# mutteruhr-Haus.net
KiCad netlist of a schematic drawn in EAGLE
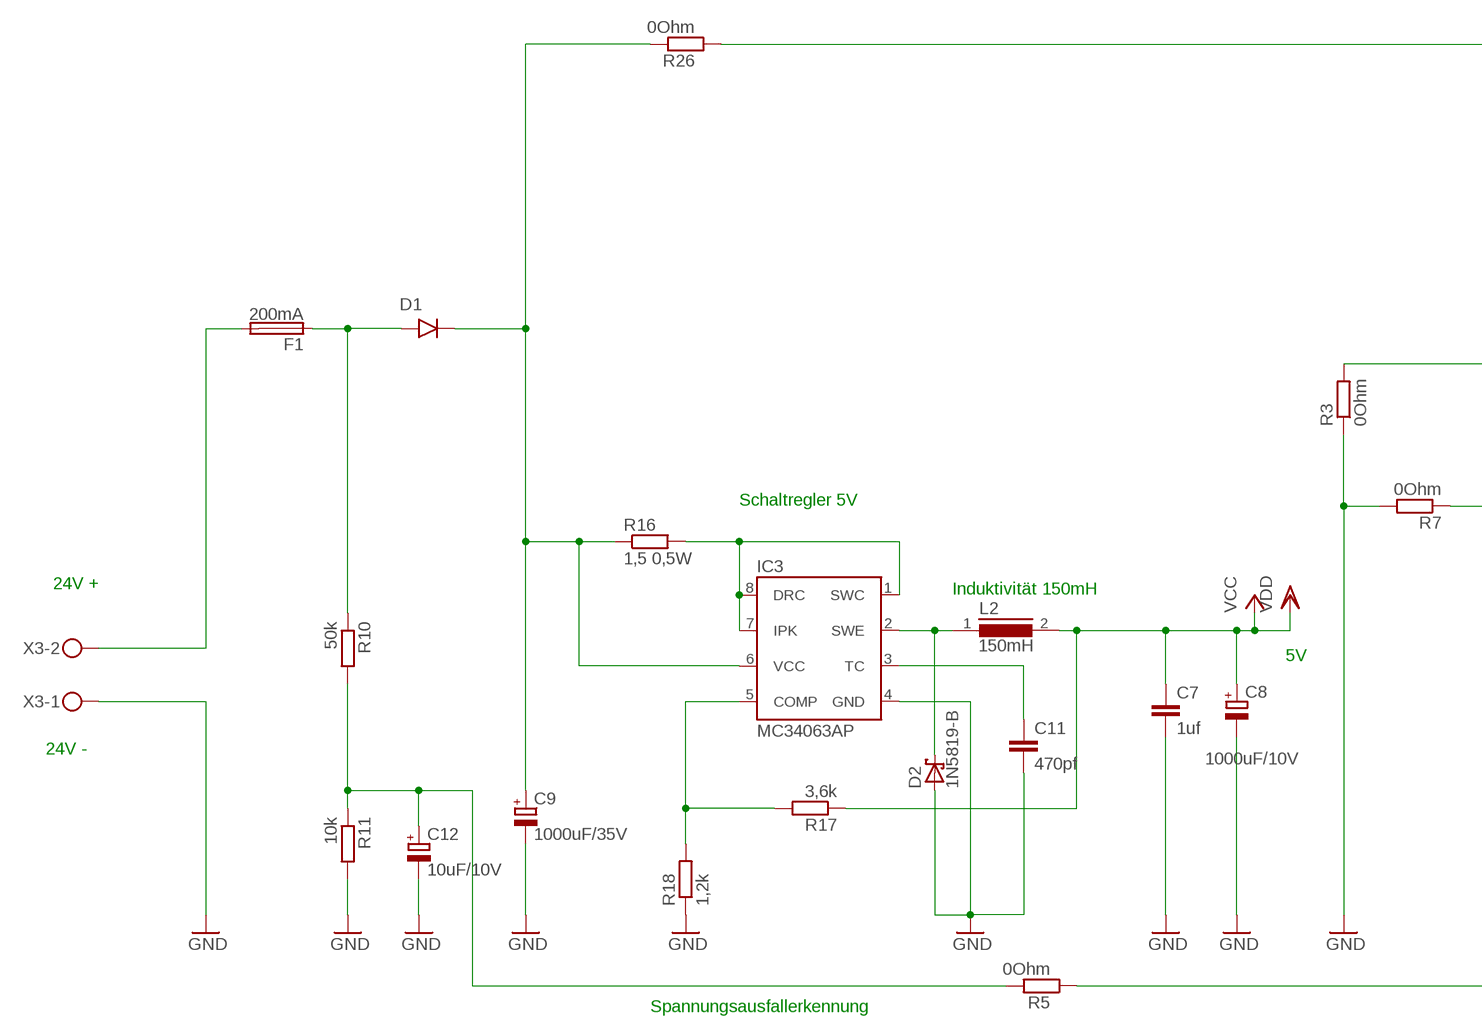
[diagram p0: schematic, sheet 1, part 1 of 2]
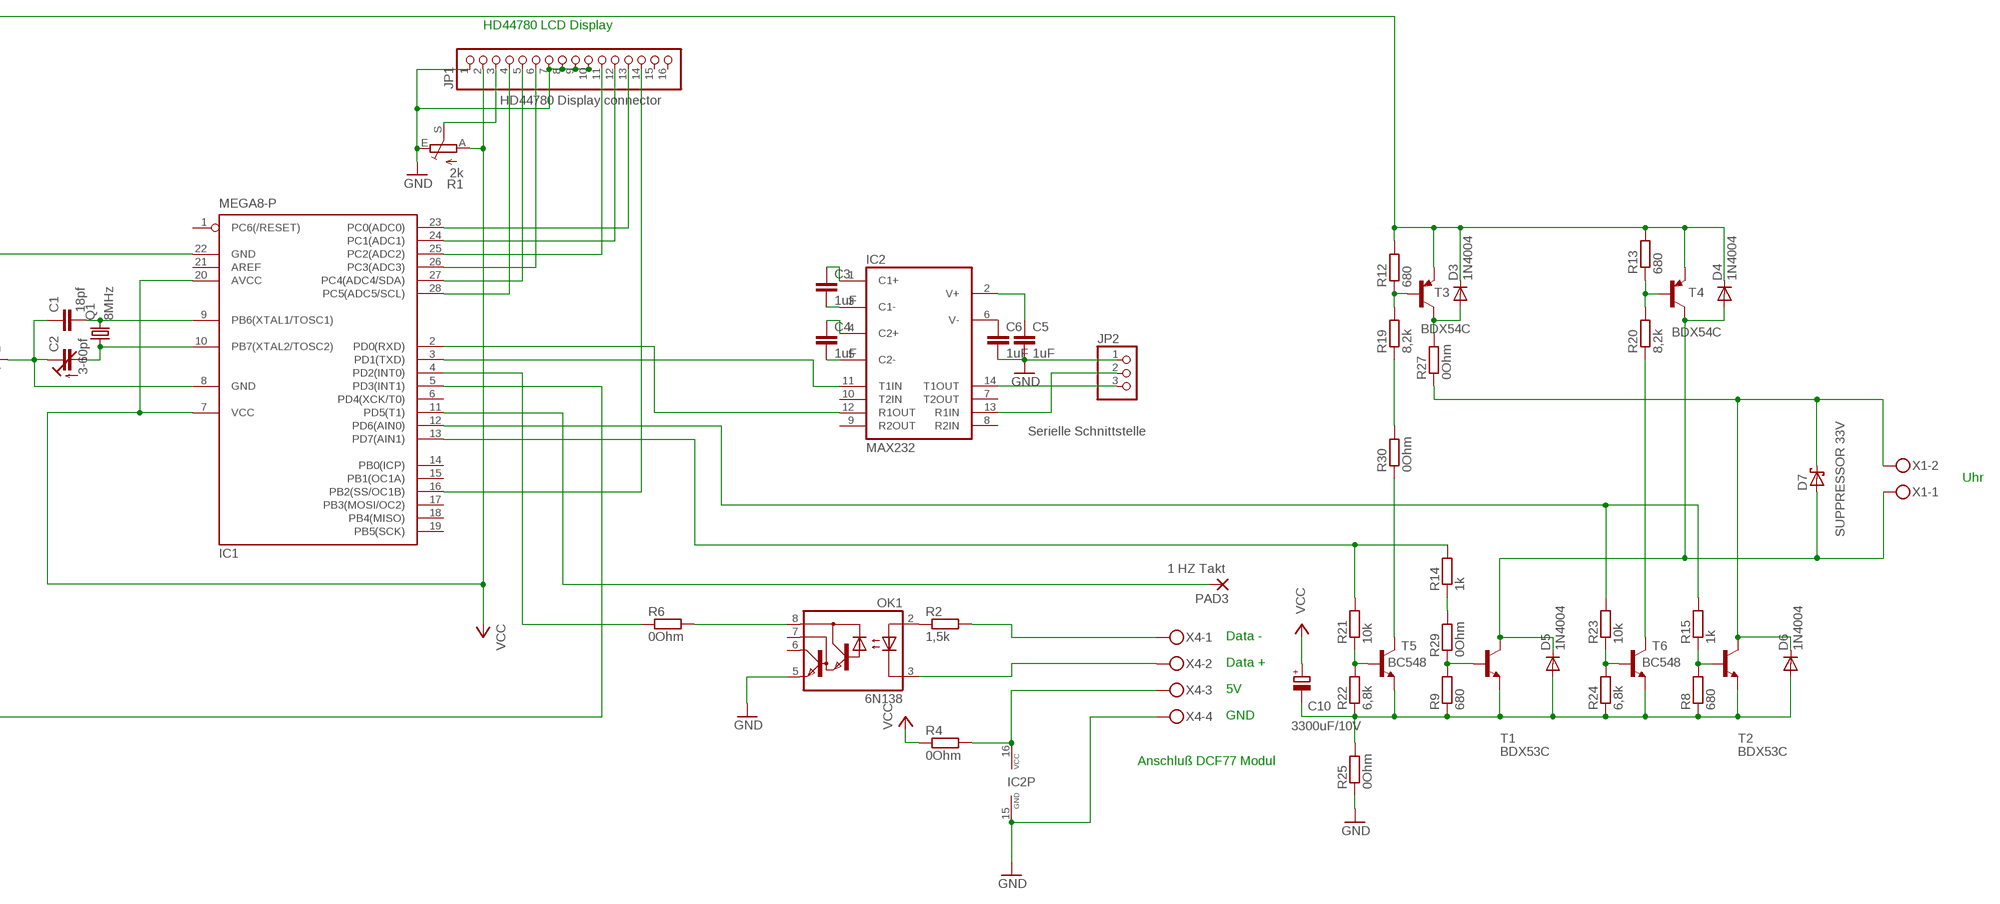
[diagram p1: schematic, sheet 1, part 2 of 2]

(export (version "E")
  (design (tool "Eeschema 10.0.6"))
  (components
    (comp (ref "C1")
      (value "18pf")
      (footprint "eagle-import:C050-024X044")
      (libsource (lib "eagle-import") (part "C-EU050-024X044"))
    )
    (comp (ref "C2")
      (value "3-60pf")
      (footprint "eagle-import:CTRIM3050.505")
      (libsource (lib "eagle-import") (part "C-TRIMM3050.505"))
    )
    (comp (ref "C3")
      (value "1uF")
      (footprint "eagle-import:C5B5.5")
      (libsource (lib "eagle-import") (part "C5/5.5"))
    )
    (comp (ref "C4")
      (value "1uF")
      (footprint "eagle-import:C5B5.5")
      (libsource (lib "eagle-import") (part "C5/5.5"))
    )
    (comp (ref "C5")
      (value "1uF")
      (footprint "eagle-import:C5B5.5")
      (libsource (lib "eagle-import") (part "C5/5.5"))
    )
    (comp (ref "C6")
      (value "1uF")
      (footprint "eagle-import:C5B5.5")
      (libsource (lib "eagle-import") (part "C5/5.5"))
    )
    (comp (ref "C7")
      (value "1uf")
      (footprint "eagle-import:C5B5.5")
      (libsource (lib "eagle-import") (part "C5/5.5"))
    )
    (comp (ref "C8")
      (value "1000uF/10V")
      (footprint "eagle-import:E5-8,5")
      (libsource (lib "eagle-import") (part "CPOL-EUE5-8.5"))
    )
    (comp (ref "C9")
      (value "1000uF/35V")
      (footprint "eagle-import:E5-8,5")
      (libsource (lib "eagle-import") (part "CPOL-EUE5-8.5"))
    )
    (comp (ref "C10")
      (value "3300uF/10V")
      (footprint "eagle-import:E7,5-16")
      (libsource (lib "eagle-import") (part "CPOL-EUE7.5-16"))
    )
    (comp (ref "C11")
      (value "470pf")
      (footprint "eagle-import:C5B5.5")
      (libsource (lib "eagle-import") (part "C5/5.5"))
    )
    (comp (ref "C12")
      (value "10uF/10V")
      (footprint "eagle-import:E5-5")
      (libsource (lib "eagle-import") (part "rcl-2_CPOL-EUE5-5"))
    )
    (comp (ref "D1")
      (value "1N4001")
      (footprint "eagle-import:DO41-10")
      (libsource (lib "eagle-import") (part "1N4001"))
    )
    (comp (ref "D2")
      (value "1N5819-B")
      (footprint "eagle-import:DO41-7.6")
      (libsource (lib "eagle-import") (part "1N5819-B"))
    )
    (comp (ref "D3")
      (value "1N4004")
      (footprint "eagle-import:DO41-10")
      (libsource (lib "eagle-import") (part "1N4004"))
    )
    (comp (ref "D4")
      (value "1N4004")
      (footprint "eagle-import:DO41-10")
      (libsource (lib "eagle-import") (part "1N4004"))
    )
    (comp (ref "D5")
      (value "1N4004")
      (footprint "eagle-import:DO41-10")
      (libsource (lib "eagle-import") (part "1N4004"))
    )
    (comp (ref "D6")
      (value "1N4004")
      (footprint "eagle-import:DO41-10")
      (libsource (lib "eagle-import") (part "1N4004"))
    )
    (comp (ref "D7")
      (value "SUPPRESSOR 33V")
      (footprint "eagle-import:DO41-10")
      (libsource (lib "eagle-import") (part "P4KEXX"))
    )
    (comp (ref "F1")
      (value "200mA")
      (footprint "eagle-import:GSH15")
      (fields (field (name "MPN") "64900001039"))
      (libsource (lib "eagle-import") (part "GSH15"))
    )
    (comp (ref "IC1")
      (value "MEGA8-P")
      (footprint "eagle-import:DIL28-3")
      (libsource (lib "eagle-import") (part "MEGA8-P"))
    )
    (comp (ref "IC2")
      (value "MAX232")
      (footprint "eagle-import:DIL16")
      (libsource (lib "eagle-import") (part "MAX232"))
    )
    (comp (ref "IC3")
      (value "MC34063AP")
      (footprint "eagle-import:DIL-08")
      (libsource (lib "eagle-import") (part "MC34063AP"))
    )
    (comp (ref "JP1")
      (value "HD44780 Display connector")
      (footprint "eagle-import:1X16")
      (libsource (lib "eagle-import") (part "PINHD-1X16_2.54"))
    )
    (comp (ref "JP2")
      (value "Serielle Schnittstelle")
      (footprint "eagle-import:1X03")
      (libsource (lib "eagle-import") (part "PINHD-1X3"))
    )
    (comp (ref "L2")
      (value "150mH")
      (footprint "eagle-import:82114R")
      (libsource (lib "eagle-import") (part "82114R"))
    )
    (comp (ref "OK1")
      (value "6N138")
      (footprint "eagle-import:DIL08")
      (fields (field (name "MF") "VISHAY/TELEFUNKEN"))
      (libsource (lib "eagle-import") (part "6N138"))
    )
    (comp (ref "PAD3")
      (value "1 HZ Takt")
      (footprint "eagle-import:2,54_0,8")
      (libsource (lib "eagle-import") (part "2,54/0,8"))
    )
    (comp (ref "Q1")
      (value "8MHz")
      (footprint "eagle-import:HC18U-V")
      (libsource (lib "eagle-import") (part "CRYSTALHC18U-V"))
    )
    (comp (ref "R1")
      (value "2k")
      (footprint "eagle-import:RS3")
      (libsource (lib "eagle-import") (part "TRIM_EU-RS3"))
    )
    (comp (ref "R2")
      (value "1,5k")
      (footprint "eagle-import:0204_7")
      (libsource (lib "eagle-import") (part "R-EU_0204/7"))
    )
    (comp (ref "R3")
      (value "0Ohm")
      (footprint "eagle-import:0204_7")
      (libsource (lib "eagle-import") (part "R-EU_0204/7"))
    )
    (comp (ref "R4")
      (value "0Ohm")
      (footprint "eagle-import:0204_7")
      (libsource (lib "eagle-import") (part "R-EU_0204/7"))
    )
    (comp (ref "R5")
      (value "0Ohm")
      (footprint "eagle-import:0204_7")
      (libsource (lib "eagle-import") (part "R-EU_0204/7"))
    )
    (comp (ref "R6")
      (value "0Ohm")
      (footprint "eagle-import:0204_7")
      (libsource (lib "eagle-import") (part "R-EU_0204/7"))
    )
    (comp (ref "R7")
      (value "0Ohm")
      (footprint "eagle-import:0204_7")
      (libsource (lib "eagle-import") (part "R-EU_0204/7"))
    )
    (comp (ref "R8")
      (value "680")
      (footprint "eagle-import:0207_10")
      (libsource (lib "eagle-import") (part "resistor_R-EU_0207/10"))
    )
    (comp (ref "R9")
      (value "680")
      (footprint "eagle-import:0207_10")
      (libsource (lib "eagle-import") (part "resistor_R-EU_0207/10"))
    )
    (comp (ref "R10")
      (value "50k")
      (footprint "eagle-import:0204_7")
      (libsource (lib "eagle-import") (part "R-EU_0204/7"))
    )
    (comp (ref "R11")
      (value "10k")
      (footprint "eagle-import:0204_7")
      (libsource (lib "eagle-import") (part "R-EU_0204/7"))
    )
    (comp (ref "R12")
      (value "680")
      (footprint "eagle-import:0207_10")
      (libsource (lib "eagle-import") (part "resistor_R-EU_0207/10"))
    )
    (comp (ref "R13")
      (value "680")
      (footprint "eagle-import:0207_10")
      (libsource (lib "eagle-import") (part "resistor_R-EU_0207/10"))
    )
    (comp (ref "R14")
      (value "1k")
      (footprint "eagle-import:0207_10")
      (libsource (lib "eagle-import") (part "resistor_R-EU_0207/10"))
    )
    (comp (ref "R15")
      (value "1k")
      (footprint "eagle-import:0207_10")
      (libsource (lib "eagle-import") (part "resistor_R-EU_0207/10"))
    )
    (comp (ref "R16")
      (value "1,5 0,5W")
      (footprint "eagle-import:0204_7")
      (libsource (lib "eagle-import") (part "R-EU_0204/7"))
    )
    (comp (ref "R17")
      (value "3,6k")
      (footprint "eagle-import:0204_7")
      (libsource (lib "eagle-import") (part "R-EU_0204/7"))
    )
    (comp (ref "R18")
      (value "1,2k")
      (footprint "eagle-import:0204_7")
      (libsource (lib "eagle-import") (part "R-EU_0204/7"))
    )
    (comp (ref "R19")
      (value "8,2k")
      (footprint "eagle-import:0207_10")
      (libsource (lib "eagle-import") (part "resistor_R-EU_0207/10"))
    )
    (comp (ref "R20")
      (value "8,2k")
      (footprint "eagle-import:0207_10")
      (libsource (lib "eagle-import") (part "resistor_R-EU_0207/10"))
    )
    (comp (ref "R21")
      (value "10k")
      (footprint "eagle-import:0207_10")
      (libsource (lib "eagle-import") (part "resistor_R-EU_0207/10"))
    )
    (comp (ref "R22")
      (value "6,8k")
      (footprint "eagle-import:0204V")
      (libsource (lib "eagle-import") (part "resistor_R-EU_0204/2V"))
    )
    (comp (ref "R23")
      (value "10k")
      (footprint "eagle-import:0207_10")
      (libsource (lib "eagle-import") (part "resistor_R-EU_0207/10"))
    )
    (comp (ref "R24")
      (value "6,8k")
      (footprint "eagle-import:0204V")
      (libsource (lib "eagle-import") (part "resistor_R-EU_0204/2V"))
    )
    (comp (ref "R25")
      (value "0Ohm")
      (footprint "eagle-import:0204_7")
      (libsource (lib "eagle-import") (part "R-EU_0204/7"))
    )
    (comp (ref "R26")
      (value "0Ohm")
      (footprint "eagle-import:0204_7")
      (libsource (lib "eagle-import") (part "R-EU_0204/7"))
    )
    (comp (ref "R27")
      (value "0Ohm")
      (footprint "eagle-import:0207_10")
      (libsource (lib "eagle-import") (part "resistor_R-EU_0207/10"))
    )
    (comp (ref "R29")
      (value "0Ohm")
      (footprint "eagle-import:0207_10")
      (libsource (lib "eagle-import") (part "resistor_R-EU_0207/10"))
    )
    (comp (ref "R30")
      (value "0Ohm")
      (footprint "eagle-import:0207_10")
      (libsource (lib "eagle-import") (part "resistor_R-EU_0207/10"))
    )
    (comp (ref "T1")
      (value "BDX53C")
      (footprint "eagle-import:TO220V")
      (libsource (lib "eagle-import") (part "-NPN-TO220V"))
    )
    (comp (ref "T2")
      (value "BDX53C")
      (footprint "eagle-import:TO220V")
      (libsource (lib "eagle-import") (part "-NPN-TO220V"))
    )
    (comp (ref "T3")
      (value "BDX54C")
      (footprint "eagle-import:TO220V")
      (libsource (lib "eagle-import") (part "-PNP-TO220V"))
    )
    (comp (ref "T4")
      (value "BDX54C")
      (footprint "eagle-import:TO220V")
      (libsource (lib "eagle-import") (part "-PNP-TO220V"))
    )
    (comp (ref "T5")
      (value "BC548")
      (footprint "eagle-import:TO92-EBC")
      (libsource (lib "eagle-import") (part "-NPN-TO92-EBC2N5551"))
    )
    (comp (ref "T6")
      (value "BC548")
      (footprint "eagle-import:TO92-EBC")
      (libsource (lib "eagle-import") (part "-NPN-TO92-EBC2N5551"))
    )
    (comp (ref "X1")
      (value "MKDSN1,5/2-5,08")
      (footprint "eagle-import:MKDSN1,5_2-5,08")
      (fields (field (name "MPN") "MKDSN 1,5/2-5.08"))
      (libsource (lib "eagle-import") (part "MKDSN1,5/2-5,08"))
    )
    (comp (ref "X3")
      (value "MKDSN1,5/2-5,08")
      (footprint "eagle-import:MKDSN1,5_2-5,08")
      (fields (field (name "MPN") "MKDSN 1,5/2-5.08"))
      (libsource (lib "eagle-import") (part "MKDSN1,5/2-5,08"))
    )
    (comp (ref "X4")
      (value "MKDSN1,5/4-5,08")
      (footprint "eagle-import:MKDSN1,5_4-5,08")
      (fields (field (name "MPN") "SMKDSN1,5/4-5,08"))
      (libsource (lib "eagle-import") (part "MKDSN1,5/4-5,08"))
    )
  )
  (nets
    (net (code "1") (name "GND") (class "Default")
      (node (ref "C11") (pin "2") (pinfunction "2_2") (pintype "passive"))
      (node (ref "C12") (pin "-") (pinfunction "-_-") (pintype "passive"))
      (node (ref "C5") (pin "2") (pinfunction "2_2") (pintype "passive"))
      (node (ref "C6") (pin "2") (pinfunction "2_2") (pintype "passive"))
      (node (ref "C7") (pin "2") (pinfunction "2_2") (pintype "passive"))
      (node (ref "C8") (pin "-") (pinfunction "-_-") (pintype "passive"))
      (node (ref "C9") (pin "-") (pinfunction "-_-") (pintype "passive"))
      (node (ref "D2") (pin "A") (pinfunction "A_A") (pintype "passive"))
      (node (ref "IC2") (pin "15") (pinfunction "GND_15") (pintype "power_in"))
      (node (ref "IC3") (pin "4") (pinfunction "GND_4") (pintype "power_in"))
      (node (ref "JP1") (pin "1") (pinfunction "1_1") (pintype "passive"))
      (node (ref "JP1") (pin "10") (pinfunction "10_10") (pintype "passive"))
      (node (ref "JP1") (pin "7") (pinfunction "7_7") (pintype "passive"))
      (node (ref "JP1") (pin "8") (pinfunction "8_8") (pintype "passive"))
      (node (ref "JP1") (pin "9") (pinfunction "9_9") (pintype "passive"))
      (node (ref "JP2") (pin "1") (pinfunction "1_1") (pintype "passive"))
      (node (ref "OK1") (pin "5") (pinfunction "GND_5") (pintype "passive"))
      (node (ref "R1") (pin "E") (pinfunction "E_E") (pintype "passive"))
      (node (ref "R11") (pin "2") (pinfunction "2_2") (pintype "passive"))
      (node (ref "R18") (pin "1") (pinfunction "1_1") (pintype "passive"))
      (node (ref "R25") (pin "1") (pinfunction "1_1") (pintype "passive"))
      (node (ref "R3") (pin "1") (pinfunction "1_1") (pintype "passive"))
      (node (ref "R7") (pin "2") (pinfunction "2_2") (pintype "passive"))
      (node (ref "X3") (pin "1") (pinfunction "KL_1") (pintype "passive"))
      (node (ref "X4") (pin "4") (pinfunction "KL_4") (pintype "passive"))
    )
    (net (code "2") (name "Net-(C2-A)") (class "Default")
      (node (ref "C2") (pin "2") (pinfunction "A_2") (pintype "passive"))
      (node (ref "IC1") (pin "10") (pinfunction "PB7(XTAL2/TOSC2)_10") (pintype "bidirectional"))
      (node (ref "Q1") (pin "1") (pinfunction "1_1") (pintype "passive"))
    )
    (net (code "3") (name "Net-(C2-E)") (class "Default")
      (node (ref "C1") (pin "1") (pinfunction "1_1") (pintype "passive"))
      (node (ref "C2") (pin "1") (pinfunction "E_1") (pintype "passive"))
      (node (ref "IC1") (pin "8") (pinfunction "GND_8") (pintype "power_in"))
      (node (ref "R7") (pin "1") (pinfunction "1_1") (pintype "passive"))
    )
    (net (code "4") (name "Net-(C12-Pad+)") (class "Default")
      (node (ref "C12") (pin "+") (pinfunction "+_+") (pintype "passive"))
      (node (ref "R10") (pin "2") (pinfunction "2_2") (pintype "passive"))
      (node (ref "R11") (pin "1") (pinfunction "1_1") (pintype "passive"))
      (node (ref "R5") (pin "2") (pinfunction "2_2") (pintype "passive"))
    )
    (net (code "5") (name "Net-(D1-ANODE)") (class "Default")
      (node (ref "D1") (pin "A") (pinfunction "ANODE_A") (pintype "passive"))
      (node (ref "F1") (pin "1") (pinfunction "1_1") (pintype "passive"))
      (node (ref "R10") (pin "1") (pinfunction "1_1") (pintype "passive"))
    )
    (net (code "6") (name "Net-(D1-CATHODE)") (class "Default")
      (node (ref "C9") (pin "+") (pinfunction "+_+") (pintype "passive"))
      (node (ref "D1") (pin "C") (pinfunction "CATHODE_C") (pintype "passive"))
      (node (ref "IC3") (pin "6") (pinfunction "VCC_6") (pintype "power_in"))
      (node (ref "R16") (pin "1") (pinfunction "1_1") (pintype "passive"))
      (node (ref "R26") (pin "2") (pinfunction "2_2") (pintype "passive"))
    )
    (net (code "7") (name "Net-(IC1-GND-Pad22)") (class "Default")
      (node (ref "IC1") (pin "22") (pinfunction "GND_22") (pintype "power_in"))
      (node (ref "R3") (pin "2") (pinfunction "2_2") (pintype "passive"))
    )
    (net (code "8") (name "Net-(IC1-PB2(SS{slash}OC1B))") (class "Default")
      (node (ref "IC1") (pin "16") (pinfunction "PB2(SS/OC1B)_16") (pintype "bidirectional"))
      (node (ref "JP1") (pin "14") (pinfunction "14_14") (pintype "passive"))
    )
    (net (code "9") (name "Net-(IC1-PB6(XTAL1{slash}TOSC1))") (class "Default")
      (node (ref "C1") (pin "2") (pinfunction "2_2") (pintype "passive"))
      (node (ref "IC1") (pin "9") (pinfunction "PB6(XTAL1/TOSC1)_9") (pintype "bidirectional"))
      (node (ref "Q1") (pin "2") (pinfunction "2_2") (pintype "passive"))
    )
    (net (code "10") (name "Net-(IC1-PC0(ADC0))") (class "Default")
      (node (ref "IC1") (pin "23") (pinfunction "PC0(ADC0)_23") (pintype "bidirectional"))
      (node (ref "JP1") (pin "13") (pinfunction "13_13") (pintype "passive"))
    )
    (net (code "11") (name "Net-(IC1-PC1(ADC1))") (class "Default")
      (node (ref "IC1") (pin "24") (pinfunction "PC1(ADC1)_24") (pintype "bidirectional"))
      (node (ref "JP1") (pin "12") (pinfunction "12_12") (pintype "passive"))
    )
    (net (code "12") (name "Net-(IC1-PC2(ADC2))") (class "Default")
      (node (ref "IC1") (pin "25") (pinfunction "PC2(ADC2)_25") (pintype "bidirectional"))
      (node (ref "JP1") (pin "11") (pinfunction "11_11") (pintype "passive"))
    )
    (net (code "13") (name "Net-(IC1-PC3(ADC3))") (class "Default")
      (node (ref "IC1") (pin "26") (pinfunction "PC3(ADC3)_26") (pintype "bidirectional"))
      (node (ref "JP1") (pin "6") (pinfunction "6_6") (pintype "passive"))
    )
    (net (code "14") (name "Net-(IC1-PC4(ADC4{slash}SDA))") (class "Default")
      (node (ref "IC1") (pin "27") (pinfunction "PC4(ADC4/SDA)_27") (pintype "bidirectional"))
      (node (ref "JP1") (pin "5") (pinfunction "5_5") (pintype "passive"))
    )
    (net (code "15") (name "Net-(IC1-PC5(ADC5{slash}SCL))") (class "Default")
      (node (ref "IC1") (pin "28") (pinfunction "PC5(ADC5/SCL)_28") (pintype "bidirectional"))
      (node (ref "JP1") (pin "4") (pinfunction "4_4") (pintype "passive"))
    )
    (net (code "16") (name "Net-(IC1-PD0(RXD))") (class "Default")
      (node (ref "IC1") (pin "2") (pinfunction "PD0(RXD)_2") (pintype "bidirectional"))
      (node (ref "IC2") (pin "12") (pinfunction "R1OUT_12") (pintype "output"))
    )
    (net (code "17") (name "Net-(IC1-PD1(TXD))") (class "Default")
      (node (ref "IC1") (pin "3") (pinfunction "PD1(TXD)_3") (pintype "bidirectional"))
      (node (ref "IC2") (pin "11") (pinfunction "T1IN_11") (pintype "input"))
    )
    (net (code "18") (name "Net-(IC1-PD2(INT0))") (class "Default")
      (node (ref "IC1") (pin "4") (pinfunction "PD2(INT0)_4") (pintype "bidirectional"))
      (node (ref "R6") (pin "1") (pinfunction "1_1") (pintype "passive"))
    )
    (net (code "19") (name "Net-(IC1-PD3(INT1))") (class "Default")
      (node (ref "IC1") (pin "5") (pinfunction "PD3(INT1)_5") (pintype "bidirectional"))
      (node (ref "R5") (pin "1") (pinfunction "1_1") (pintype "passive"))
    )
    (net (code "20") (name "Net-(IC1-PD5(T1))") (class "Default")
      (node (ref "IC1") (pin "11") (pinfunction "PD5(T1)_11") (pintype "bidirectional"))
      (node (ref "PAD3") (pin "1") (pinfunction "P_1") (pintype "passive"))
    )
    (net (code "21") (name "Net-(IC1-PD6(AIN0))") (class "Default")
      (node (ref "IC1") (pin "12") (pinfunction "PD6(AIN0)_12") (pintype "bidirectional"))
      (node (ref "R15") (pin "2") (pinfunction "2_2") (pintype "passive"))
      (node (ref "R23") (pin "2") (pinfunction "2_2") (pintype "passive"))
    )
    (net (code "22") (name "Net-(IC1-PD7(AIN1))") (class "Default")
      (node (ref "IC1") (pin "13") (pinfunction "PD7(AIN1)_13") (pintype "bidirectional"))
      (node (ref "R14") (pin "2") (pinfunction "2_2") (pintype "passive"))
      (node (ref "R21") (pin "2") (pinfunction "2_2") (pintype "passive"))
    )
    (net (code "23") (name "Net-(IC2A-C1+)") (class "Default")
      (node (ref "C3") (pin "1") (pinfunction "1_1") (pintype "passive"))
      (node (ref "IC2") (pin "1") (pinfunction "C1+_1") (pintype "bidirectional"))
    )
    (net (code "24") (name "Net-(IC2A-C1-)") (class "Default")
      (node (ref "C3") (pin "2") (pinfunction "2_2") (pintype "passive"))
      (node (ref "IC2") (pin "3") (pinfunction "C1-_3") (pintype "bidirectional"))
    )
    (net (code "25") (name "Net-(IC2A-C2+)") (class "Default")
      (node (ref "C4") (pin "1") (pinfunction "1_1") (pintype "passive"))
      (node (ref "IC2") (pin "4") (pinfunction "C2+_4") (pintype "bidirectional"))
    )
    (net (code "26") (name "Net-(IC2A-C2-)") (class "Default")
      (node (ref "C4") (pin "2") (pinfunction "2_2") (pintype "passive"))
      (node (ref "IC2") (pin "5") (pinfunction "C2-_5") (pintype "bidirectional"))
    )
    (net (code "27") (name "Net-(IC2A-R1IN)") (class "Default")
      (node (ref "IC2") (pin "13") (pinfunction "R1IN_13") (pintype "input"))
      (node (ref "JP2") (pin "2") (pinfunction "2_2") (pintype "passive"))
    )
    (net (code "28") (name "Net-(IC2A-T1OUT)") (class "Default")
      (node (ref "IC2") (pin "14") (pinfunction "T1OUT_14") (pintype "output"))
      (node (ref "JP2") (pin "3") (pinfunction "3_3") (pintype "passive"))
    )
    (net (code "29") (name "Net-(IC2A-V+)") (class "Default")
      (node (ref "C5") (pin "1") (pinfunction "1_1") (pintype "passive"))
      (node (ref "IC2") (pin "2") (pinfunction "V+_2") (pintype "bidirectional"))
    )
    (net (code "30") (name "Net-(IC2A-V-)") (class "Default")
      (node (ref "C6") (pin "1") (pinfunction "1_1") (pintype "passive"))
      (node (ref "IC2") (pin "6") (pinfunction "V-_6") (pintype "bidirectional"))
    )
    (net (code "31") (name "Net-(IC2B-VCC)") (class "Default")
      (node (ref "IC2") (pin "16") (pinfunction "VCC_16") (pintype "power_in"))
      (node (ref "R4") (pin "2") (pinfunction "2_2") (pintype "passive"))
      (node (ref "X4") (pin "3") (pinfunction "KL_3") (pintype "passive"))
    )
    (net (code "32") (name "Net-(IC3-COMP)") (class "Default")
      (node (ref "IC3") (pin "5") (pinfunction "COMP_5") (pintype "input"))
      (node (ref "R17") (pin "2") (pinfunction "2_2") (pintype "passive"))
      (node (ref "R18") (pin "2") (pinfunction "2_2") (pintype "passive"))
    )
    (net (code "33") (name "Net-(IC3-DRC)") (class "Default")
      (node (ref "IC3") (pin "1") (pinfunction "SWC_1") (pintype "bidirectional"))
      (node (ref "IC3") (pin "7") (pinfunction "IPK_7") (pintype "input"))
      (node (ref "IC3") (pin "8") (pinfunction "DRC_8") (pintype "input"))
      (node (ref "R16") (pin "2") (pinfunction "2_2") (pintype "passive"))
    )
    (net (code "34") (name "Net-(IC3-SWE)") (class "Default")
      (node (ref "D2") (pin "C") (pinfunction "C_C") (pintype "passive"))
      (node (ref "IC3") (pin "2") (pinfunction "SWE_2") (pintype "bidirectional"))
      (node (ref "L2") (pin "1") (pinfunction "1_1") (pintype "passive"))
    )
    (net (code "35") (name "Net-(IC3-TC)") (class "Default")
      (node (ref "C11") (pin "1") (pinfunction "1_1") (pintype "passive"))
      (node (ref "IC3") (pin "3") (pinfunction "TC_3") (pintype "passive"))
    )
    (net (code "36") (name "Net-(JP1-Pad3)") (class "Default")
      (node (ref "JP1") (pin "3") (pinfunction "3_3") (pintype "passive"))
      (node (ref "R1") (pin "S") (pinfunction "S_S") (pintype "passive"))
    )
    (net (code "37") (name "Net-(OK1-A)") (class "Default")
      (node (ref "OK1") (pin "2") (pinfunction "A_2") (pintype "passive"))
      (node (ref "R2") (pin "1") (pinfunction "1_1") (pintype "passive"))
    )
    (net (code "38") (name "Net-(OK1-C)") (class "Default")
      (node (ref "OK1") (pin "3") (pinfunction "C_3") (pintype "passive"))
      (node (ref "X4") (pin "2") (pinfunction "KL_2") (pintype "passive"))
    )
    (net (code "39") (name "Net-(OK1-VCC)") (class "Default")
      (node (ref "OK1") (pin "8") (pinfunction "VCC_8") (pintype "passive"))
      (node (ref "R6") (pin "2") (pinfunction "2_2") (pintype "passive"))
    )
    (net (code "40") (name "Net-(R14-Pad1)") (class "Default")
      (node (ref "R14") (pin "1") (pinfunction "1_1") (pintype "passive"))
      (node (ref "R29") (pin "2") (pinfunction "2_2") (pintype "passive"))
    )
    (net (code "41") (name "Net-(R19-Pad1)") (class "Default")
      (node (ref "R19") (pin "1") (pinfunction "1_1") (pintype "passive"))
      (node (ref "R30") (pin "2") (pinfunction "2_2") (pintype "passive"))
    )
    (net (code "42") (name "Net-(R20-Pad1)") (class "Default")
      (node (ref "R20") (pin "1") (pinfunction "1_1") (pintype "passive"))
      (node (ref "T6") (pin "C") (pinfunction "C_C") (pintype "passive"))
    )
    (net (code "43") (name "Net-(R21-Pad1)") (class "Default")
      (node (ref "R21") (pin "1") (pinfunction "1_1") (pintype "passive"))
      (node (ref "R22") (pin "2") (pinfunction "2_2") (pintype "passive"))
      (node (ref "T5") (pin "B") (pinfunction "B_B") (pintype "passive"))
    )
    (net (code "44") (name "Net-(R23-Pad1)") (class "Default")
      (node (ref "R23") (pin "1") (pinfunction "1_1") (pintype "passive"))
      (node (ref "R24") (pin "2") (pinfunction "2_2") (pintype "passive"))
      (node (ref "T6") (pin "B") (pinfunction "B_B") (pintype "passive"))
    )
    (net (code "45") (name "Net-(R30-Pad1)") (class "Default")
      (node (ref "R30") (pin "1") (pinfunction "1_1") (pintype "passive"))
      (node (ref "T5") (pin "C") (pinfunction "C_C") (pintype "passive"))
    )
    (net (code "46") (name "Net-(T1-B)") (class "Default")
      (node (ref "R29") (pin "1") (pinfunction "1_1") (pintype "passive"))
      (node (ref "R9") (pin "2") (pinfunction "2_2") (pintype "passive"))
      (node (ref "T1") (pin "1") (pinfunction "B_1") (pintype "passive"))
    )
    (net (code "47") (name "Net-(T1-C)") (class "Default")
      (node (ref "D4") (pin "A") (pinfunction "A_A") (pintype "passive"))
      (node (ref "D5") (pin "C") (pinfunction "C_C") (pintype "passive"))
      (node (ref "D7") (pin "A") (pinfunction "A_A") (pintype "passive"))
      (node (ref "T1") (pin "2") (pinfunction "C_2") (pintype "passive"))
      (node (ref "T4") (pin "2") (pinfunction "C_2") (pintype "passive"))
      (node (ref "X1") (pin "1") (pinfunction "KL_1") (pintype "passive"))
    )
    (net (code "48") (name "Net-(T1-E)") (class "Default")
      (node (ref "C10") (pin "-") (pinfunction "-_-") (pintype "passive"))
      (node (ref "D5") (pin "A") (pinfunction "A_A") (pintype "passive"))
      (node (ref "D6") (pin "A") (pinfunction "A_A") (pintype "passive"))
      (node (ref "R22") (pin "1") (pinfunction "1_1") (pintype "passive"))
      (node (ref "R24") (pin "1") (pinfunction "1_1") (pintype "passive"))
      (node (ref "R25") (pin "2") (pinfunction "2_2") (pintype "passive"))
      (node (ref "R8") (pin "1") (pinfunction "1_1") (pintype "passive"))
      (node (ref "R9") (pin "1") (pinfunction "1_1") (pintype "passive"))
      (node (ref "T1") (pin "3") (pinfunction "E_3") (pintype "passive"))
      (node (ref "T2") (pin "3") (pinfunction "E_3") (pintype "passive"))
      (node (ref "T5") (pin "E") (pinfunction "E_E") (pintype "passive"))
      (node (ref "T6") (pin "E") (pinfunction "E_E") (pintype "passive"))
    )
    (net (code "49") (name "Net-(T2-B)") (class "Default")
      (node (ref "R15") (pin "1") (pinfunction "1_1") (pintype "passive"))
      (node (ref "R8") (pin "2") (pinfunction "2_2") (pintype "passive"))
      (node (ref "T2") (pin "1") (pinfunction "B_1") (pintype "passive"))
    )
    (net (code "50") (name "Net-(T2-C)") (class "Default")
      (node (ref "D6") (pin "C") (pinfunction "C_C") (pintype "passive"))
      (node (ref "D7") (pin "C") (pinfunction "C_C") (pintype "passive"))
      (node (ref "R27") (pin "1") (pinfunction "1_1") (pintype "passive"))
      (node (ref "T2") (pin "2") (pinfunction "C_2") (pintype "passive"))
      (node (ref "X1") (pin "2") (pinfunction "KL_2") (pintype "passive"))
    )
    (net (code "51") (name "Net-(T3-B)") (class "Default")
      (node (ref "R12") (pin "1") (pinfunction "1_1") (pintype "passive"))
      (node (ref "R19") (pin "2") (pinfunction "2_2") (pintype "passive"))
      (node (ref "T3") (pin "1") (pinfunction "B_1") (pintype "passive"))
    )
    (net (code "52") (name "Net-(T3-C)") (class "Default")
      (node (ref "D3") (pin "A") (pinfunction "A_A") (pintype "passive"))
      (node (ref "R27") (pin "2") (pinfunction "2_2") (pintype "passive"))
      (node (ref "T3") (pin "2") (pinfunction "C_2") (pintype "passive"))
    )
    (net (code "53") (name "Net-(T3-E)") (class "Default")
      (node (ref "D3") (pin "C") (pinfunction "C_C") (pintype "passive"))
      (node (ref "D4") (pin "C") (pinfunction "C_C") (pintype "passive"))
      (node (ref "R12") (pin "2") (pinfunction "2_2") (pintype "passive"))
      (node (ref "R13") (pin "2") (pinfunction "2_2") (pintype "passive"))
      (node (ref "R26") (pin "1") (pinfunction "1_1") (pintype "passive"))
      (node (ref "T3") (pin "3") (pinfunction "E_3") (pintype "passive"))
      (node (ref "T4") (pin "3") (pinfunction "E_3") (pintype "passive"))
    )
    (net (code "54") (name "Net-(T4-B)") (class "Default")
      (node (ref "R13") (pin "1") (pinfunction "1_1") (pintype "passive"))
      (node (ref "R20") (pin "2") (pinfunction "2_2") (pintype "passive"))
      (node (ref "T4") (pin "1") (pinfunction "B_1") (pintype "passive"))
    )
    (net (code "55") (name "Net-(X3B-KL)") (class "Default")
      (node (ref "F1") (pin "2") (pinfunction "2_2") (pintype "passive"))
      (node (ref "X3") (pin "2") (pinfunction "KL_2") (pintype "passive"))
    )
    (net (code "56") (name "Net-(X4A-KL)") (class "Default")
      (node (ref "R2") (pin "2") (pinfunction "2_2") (pintype "passive"))
      (node (ref "X4") (pin "1") (pinfunction "KL_1") (pintype "passive"))
    )
    (net (code "57") (name "VCC") (class "Default")
      (node (ref "C10") (pin "+") (pinfunction "+_+") (pintype "passive"))
      (node (ref "C7") (pin "1") (pinfunction "1_1") (pintype "passive"))
      (node (ref "C8") (pin "+") (pinfunction "+_+") (pintype "passive"))
      (node (ref "IC1") (pin "20") (pinfunction "AVCC_20") (pintype "power_in"))
      (node (ref "IC1") (pin "7") (pinfunction "VCC_7") (pintype "power_in"))
      (node (ref "JP1") (pin "2") (pinfunction "2_2") (pintype "passive"))
      (node (ref "L2") (pin "2") (pinfunction "2_2") (pintype "passive"))
      (node (ref "R1") (pin "A") (pinfunction "A_A") (pintype "passive"))
      (node (ref "R17") (pin "1") (pinfunction "1_1") (pintype "passive"))
      (node (ref "R4") (pin "1") (pinfunction "1_1") (pintype "passive"))
    )
    (net (code "58") (name "unconnected-(IC1-AREF-Pad21)") (class "Default")
      (node (ref "IC1") (pin "21") (pinfunction "AREF_21") (pintype "passive"))
    )
    (net (code "59") (name "unconnected-(IC1-PB0(ICP)-Pad14)") (class "Default")
      (node (ref "IC1") (pin "14") (pinfunction "PB0(ICP)_14") (pintype "bidirectional"))
    )
    (net (code "60") (name "unconnected-(IC1-PB1(OC1A)-Pad15)") (class "Default")
      (node (ref "IC1") (pin "15") (pinfunction "PB1(OC1A)_15") (pintype "bidirectional"))
    )
    (net (code "61") (name "unconnected-(IC1-PB3(MOSI{slash}OC2)-Pad17)") (class "Default")
      (node (ref "IC1") (pin "17") (pinfunction "PB3(MOSI/OC2)_17") (pintype "bidirectional"))
    )
    (net (code "62") (name "unconnected-(IC1-PB4(MISO)-Pad18)") (class "Default")
      (node (ref "IC1") (pin "18") (pinfunction "PB4(MISO)_18") (pintype "bidirectional"))
    )
    (net (code "63") (name "unconnected-(IC1-PB5(SCK)-Pad19)") (class "Default")
      (node (ref "IC1") (pin "19") (pinfunction "PB5(SCK)_19") (pintype "bidirectional"))
    )
    (net (code "64") (name "unconnected-(IC1-PC6({slash}RESET)-Pad1)") (class "Default")
      (node (ref "IC1") (pin "1") (pinfunction "PC6(/RESET)_1") (pintype "bidirectional"))
    )
    (net (code "65") (name "unconnected-(IC1-PD4(XCK{slash}T0)-Pad6)") (class "Default")
      (node (ref "IC1") (pin "6") (pinfunction "PD4(XCK/T0)_6") (pintype "bidirectional"))
    )
    (net (code "66") (name "unconnected-(IC2A-R2IN-Pad8)") (class "Default")
      (node (ref "IC2") (pin "8") (pinfunction "R2IN_8") (pintype "input"))
    )
    (net (code "67") (name "unconnected-(IC2A-R2OUT-Pad9)") (class "Default")
      (node (ref "IC2") (pin "9") (pinfunction "R2OUT_9") (pintype "output"))
    )
    (net (code "68") (name "unconnected-(IC2A-T2IN-Pad10)") (class "Default")
      (node (ref "IC2") (pin "10") (pinfunction "T2IN_10") (pintype "input"))
    )
    (net (code "69") (name "unconnected-(IC2A-T2OUT-Pad7)") (class "Default")
      (node (ref "IC2") (pin "7") (pinfunction "T2OUT_7") (pintype "output"))
    )
    (net (code "70") (name "unconnected-(JP1-Pad15)") (class "Default")
      (node (ref "JP1") (pin "15") (pinfunction "15_15") (pintype "passive"))
    )
    (net (code "71") (name "unconnected-(JP1-Pad16)") (class "Default")
      (node (ref "JP1") (pin "16") (pinfunction "16_16") (pintype "passive"))
    )
    (net (code "72") (name "unconnected-(OK1-VB-Pad7)") (class "Default")
      (node (ref "OK1") (pin "7") (pinfunction "VB_7") (pintype "passive"))
    )
    (net (code "73") (name "unconnected-(OK1-VO-Pad6)") (class "Default")
      (node (ref "OK1") (pin "6") (pinfunction "VO_6") (pintype "passive"))
    )
  )
)
